# sch.net
KiCad netlist of a schematic drawn in Altium Designer
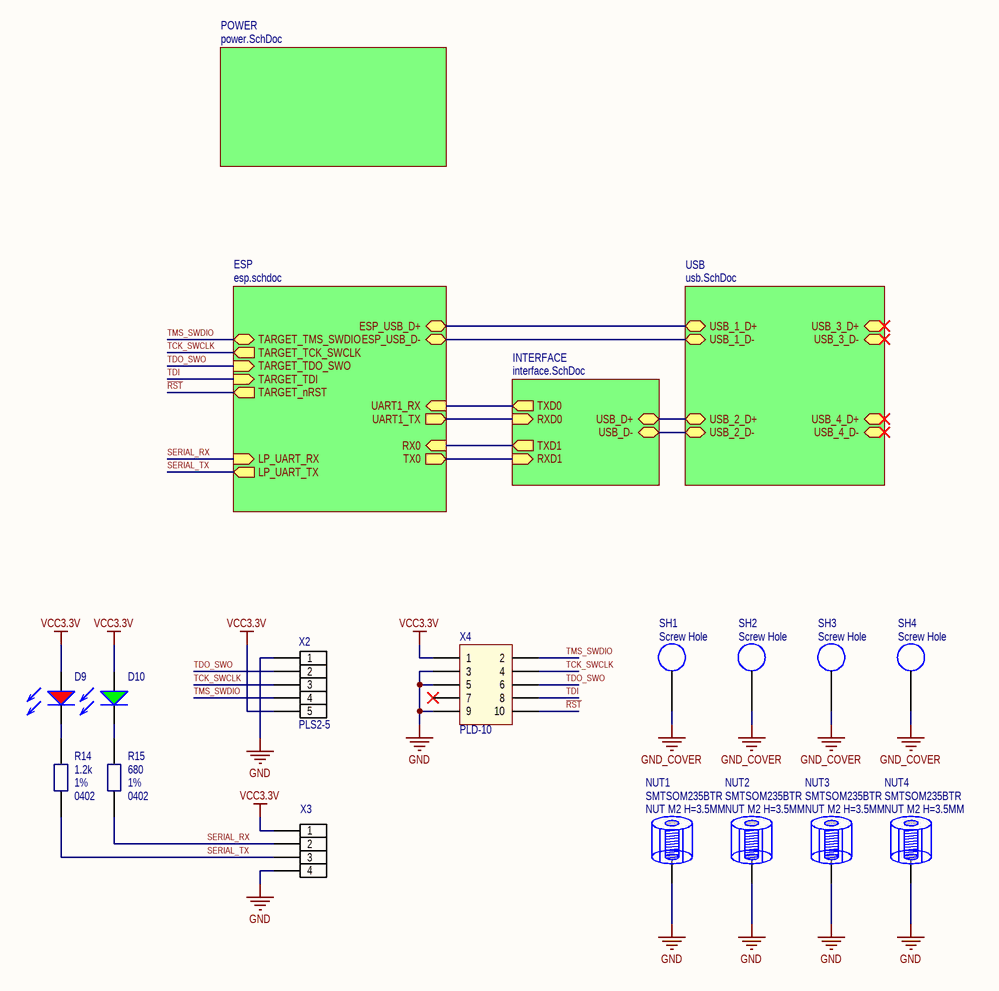
[diagram p0: sch.SchDoc]

(export (version "E")
  (design (tool "Eeschema 10.0.6"))
  (components
    (comp (ref "D9")
      (value "Red 645nm")
      (footprint "LED 0603 RED, 60°")
      (description "RED LED 0603, 60°")
      (fields (field (name "PART") "APTD1608LSURCK"))
      (libsource (lib "led_lcd") (part "RED-LED-0603"))
    )
    (comp (ref "D10")
      (value "Emerald Green 515nm")
      (footprint "LED 0603 GREEN, 60°")
      (description "GREEN LED 0603, 60°")
      (fields (field (name "PART") "APTD1608ZGC"))
      (libsource (lib "led_lcd") (part "GREEN LED 0603"))
    )
    (comp (ref "NUT1")
      (value "SMTSOM235BTR")
      (footprint "SMTSOM235BTR")
      (description "NUT M2 H=3.5MM, Connector Standoff")
      (fields
        (field (name "MANUFACTURER") "Sinhoo")
        (field (name "CASE/PACKAGE") "NUT M2 H=3.5MM")
        (field (name "VERIFIED BY ME") "NO")
      )
      (libsource (lib "connectors_socets") (part "SMTSOM235BTR"))
    )
    (comp (ref "NUT2")
      (value "SMTSOM235BTR")
      (footprint "SMTSOM235BTR")
      (description "NUT M2 H=3.5MM, Connector Standoff")
      (fields
        (field (name "MANUFACTURER") "Sinhoo")
        (field (name "CASE/PACKAGE") "NUT M2 H=3.5MM")
        (field (name "VERIFIED BY ME") "NO")
      )
      (libsource (lib "connectors_socets") (part "SMTSOM235BTR"))
    )
    (comp (ref "NUT3")
      (value "SMTSOM235BTR")
      (footprint "SMTSOM235BTR")
      (description "NUT M2 H=3.5MM, Connector Standoff")
      (fields
        (field (name "MANUFACTURER") "Sinhoo")
        (field (name "CASE/PACKAGE") "NUT M2 H=3.5MM")
        (field (name "VERIFIED BY ME") "NO")
      )
      (libsource (lib "connectors_socets") (part "SMTSOM235BTR"))
    )
    (comp (ref "NUT4")
      (value "SMTSOM235BTR")
      (footprint "SMTSOM235BTR")
      (description "NUT M2 H=3.5MM, Connector Standoff")
      (fields
        (field (name "MANUFACTURER") "Sinhoo")
        (field (name "CASE/PACKAGE") "NUT M2 H=3.5MM")
        (field (name "VERIFIED BY ME") "NO")
      )
      (libsource (lib "connectors_socets") (part "SMTSOM235BTR"))
    )
    (comp (ref "R14")
      (value "1.2k")
      (footprint "R_0402")
      (description "Resistor")
      (fields
        (field (name "PART") "RC0402FR-071K2L")
        (field (name "CASE/PACKAGE") "0402")
        (field (name "TOLERANCE") "1%")
        (field (name "Comment") "R0402")
      )
      (libsource (lib "resistors") (part "R0402"))
    )
    (comp (ref "R15")
      (value "680")
      (footprint "R_0402")
      (description "Resistor")
      (fields
        (field (name "PART") "RC0402FR-07680RL")
        (field (name "CASE/PACKAGE") "0402")
        (field (name "TOLERANCE") "1%")
        (field (name "Comment") "R0402")
      )
      (libsource (lib "resistors") (part "R0402"))
    )
    (comp (ref "SH1")
      (value "Screw Hole")
      (footprint "Screw Hole 2.1mm/4.2mm")
      (libsource (lib "connectors_socets") (part "Screw Hole"))
    )
    (comp (ref "SH2")
      (value "Screw Hole")
      (footprint "Screw Hole 2.1mm/4.2mm")
      (libsource (lib "connectors_socets") (part "Screw Hole"))
    )
    (comp (ref "SH3")
      (value "Screw Hole")
      (footprint "Screw Hole 2.1mm/4.2mm")
      (libsource (lib "connectors_socets") (part "Screw Hole"))
    )
    (comp (ref "SH4")
      (value "Screw Hole")
      (footprint "Screw Hole 2.1mm/4.2mm")
      (libsource (lib "connectors_socets") (part "Screw Hole"))
    )
    (comp (ref "X2")
      (value "PLS2-5")
      (footprint "PLS-5T")
      (description "Header, 5-Pin")
      (fields (field (name "PART") "X6511WRS-05H-C60D48") (field (name "PUBLISHER") "Altium Limited"))
      (libsource (lib "connectors_socets") (part "PLS2-5"))
    )
    (comp (ref "X3")
      (value "PLS2-4")
      (footprint "PLS-4T")
      (description "Header, 4-Pin")
      (fields (field (name "PART") "X6511WRS-04H-C60D48") (field (name "PUBLISHER") "Altium Limited"))
      (libsource (lib "connectors_socets") (part "PLS2-4"))
    )
    (comp (ref "X4")
      (value "PLD-10")
      (footprint "PLD-10T")
      (description "male; PIN: 10; 2.54mm")
      (libsource (lib "connectors_socets") (part "PLD-10"))
    )
  )
  (nets
    (net (code "3") (name "/RST") (class "Default")
      (node (ref "X4") (pin "10") (pinfunction "10_10") (pintype "passive"))
    )
    (net (code "4") (name "/SERIAL_RX") (class "Default")
      (node (ref "R15") (pin "1") (pinfunction "1_1") (pintype "passive"))
      (node (ref "X3") (pin "2") (pinfunction "2_2") (pintype "passive"))
    )
    (net (code "5") (name "/SERIAL_TX") (class "Default")
      (node (ref "R14") (pin "1") (pinfunction "1_1") (pintype "passive"))
      (node (ref "X3") (pin "3") (pinfunction "3_3") (pintype "passive"))
    )
    (net (code "6") (name "/TCK_SWCLK") (class "Default")
      (node (ref "X2") (pin "3") (pinfunction "3_3") (pintype "passive"))
      (node (ref "X4") (pin "4") (pinfunction "4_4") (pintype "passive"))
    )
    (net (code "7") (name "/TDI") (class "Default")
      (node (ref "X4") (pin "8") (pinfunction "8_8") (pintype "passive"))
    )
    (net (code "8") (name "/TDO_SWO") (class "Default")
      (node (ref "X2") (pin "2") (pinfunction "2_2") (pintype "passive"))
      (node (ref "X4") (pin "6") (pinfunction "6_6") (pintype "passive"))
    )
    (net (code "9") (name "/TMS_SWDIO") (class "Default")
      (node (ref "X2") (pin "4") (pinfunction "4_4") (pintype "passive"))
      (node (ref "X4") (pin "2") (pinfunction "2_2") (pintype "passive"))
    )
    (net (code "20") (name "GND") (class "Default")
      (node (ref "NUT1") (pin "1") (pinfunction "M3_1") (pintype "passive"))
      (node (ref "NUT2") (pin "1") (pinfunction "M3_1") (pintype "passive"))
      (node (ref "NUT3") (pin "1") (pinfunction "M3_1") (pintype "passive"))
      (node (ref "NUT4") (pin "1") (pinfunction "M3_1") (pintype "passive"))
      (node (ref "X2") (pin "1") (pinfunction "1_1") (pintype "passive"))
      (node (ref "X3") (pin "4") (pinfunction "4_4") (pintype "passive"))
      (node (ref "X4") (pin "3") (pinfunction "3_3") (pintype "passive"))
      (node (ref "X4") (pin "5") (pinfunction "5_5") (pintype "passive"))
      (node (ref "X4") (pin "9") (pinfunction "9_9") (pintype "passive"))
    )
    (net (code "21") (name "GND_COVER") (class "Default")
      (node (ref "SH1") (pin "1") (pinfunction "1_1") (pintype "passive"))
      (node (ref "SH2") (pin "1") (pinfunction "1_1") (pintype "passive"))
      (node (ref "SH3") (pin "1") (pinfunction "1_1") (pintype "passive"))
      (node (ref "SH4") (pin "1") (pinfunction "1_1") (pintype "passive"))
    )
    (net (code "22") (name "Net-(D9-Pad1)") (class "Default")
      (node (ref "D9") (pin "1") (pinfunction "1_1") (pintype "passive"))
      (node (ref "R14") (pin "2") (pinfunction "2_2") (pintype "passive"))
    )
    (net (code "23") (name "Net-(D10-Pad1)") (class "Default")
      (node (ref "D10") (pin "1") (pinfunction "1_1") (pintype "passive"))
      (node (ref "R15") (pin "2") (pinfunction "2_2") (pintype "passive"))
    )
    (net (code "24") (name "VCC3.3V") (class "Default")
      (node (ref "D10") (pin "2") (pinfunction "2_2") (pintype "passive"))
      (node (ref "D9") (pin "2") (pinfunction "2_2") (pintype "passive"))
      (node (ref "X2") (pin "5") (pinfunction "5_5") (pintype "passive"))
      (node (ref "X3") (pin "1") (pinfunction "1_1") (pintype "passive"))
      (node (ref "X4") (pin "1") (pinfunction "1_1") (pintype "passive"))
    )
    (net (code "25") (name "unconnected-(X4-Pad7)") (class "Default")
      (node (ref "X4") (pin "7") (pinfunction "7_7") (pintype "passive+no_connect"))
    )
  )
)
